# tick-display-mk-3-mini.net
KiCad netlist of a schematic drawn in EAGLE
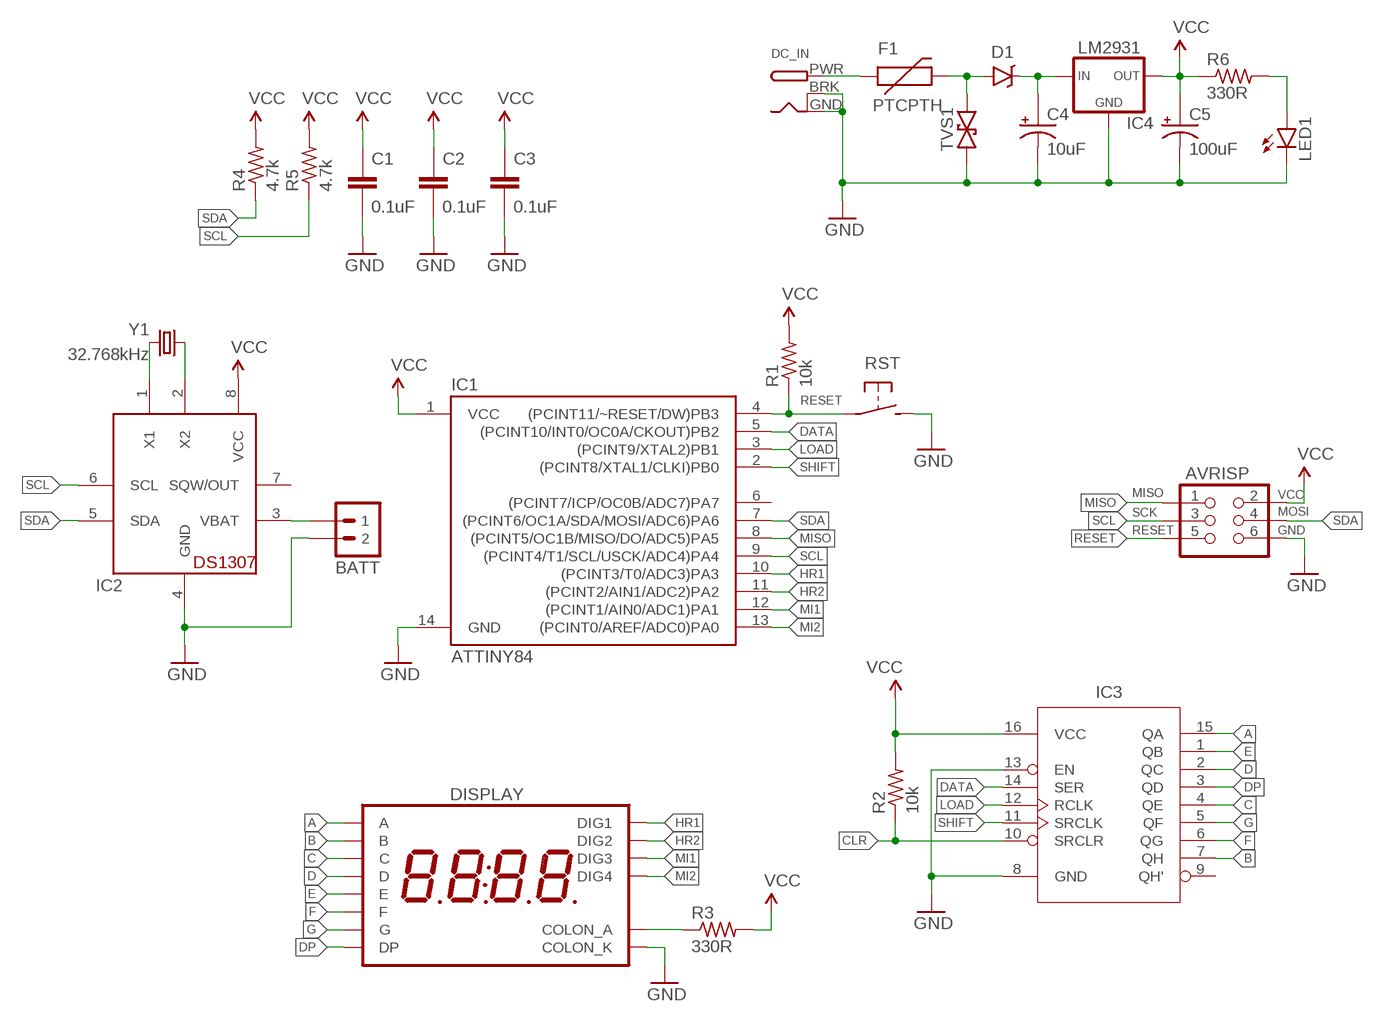
[diagram p0: schematic, sheet 1]

(export (version "E")
  (design (tool "Eeschema 10.0.6"))
  (components
    (comp (ref "AVRISP")
      (value "AVR_SPI_PRG_6PTH")
      (footprint "eagle-import:2X3")
      (libsource (lib "eagle-import") (part "AVR_SPI_PRG_6PTH"))
    )
    (comp (ref "BATT")
      (value "M02JST-PTH-VERT")
      (footprint "eagle-import:JST-2-PH-VERT-PTH")
      (libsource (lib "eagle-import") (part "M02JST-PTH-VERT"))
    )
    (comp (ref "C1")
      (value "0.1uF")
      (footprint "eagle-import:C025-024X044")
      (libsource (lib "eagle-import") (part "CAPACITOR-CERAMIC025-024X044"))
    )
    (comp (ref "C2")
      (value "0.1uF")
      (footprint "eagle-import:C025-024X044")
      (libsource (lib "eagle-import") (part "CAPACITOR-CERAMIC025-024X044"))
    )
    (comp (ref "C3")
      (value "0.1uF")
      (footprint "eagle-import:C025-024X044")
      (libsource (lib "eagle-import") (part "CAPACITOR-CERAMIC025-024X044"))
    )
    (comp (ref "C4")
      (value "10uF")
      (footprint "eagle-import:E2,5-6")
      (libsource (lib "eagle-import") (part "CAPACITOR-POLARIZEDE2.5-6"))
    )
    (comp (ref "C5")
      (value "100uF")
      (footprint "eagle-import:E2,5-6")
      (libsource (lib "eagle-import") (part "CAPACITOR-POLARIZEDE2.5-6"))
    )
    (comp (ref "D1")
      (value "1N5819")
      (footprint "eagle-import:DIODE-7.68MM")
      (libsource (lib "eagle-import") (part "DIODE-SCHOTTKYPTH-7.68MM"))
    )
    (comp (ref "DC_IN")
      (value "DCBARRELPTH")
      (footprint "eagle-import:DCJACK_2MM_PTH")
      (libsource (lib "eagle-import") (part "DCBARRELPTH"))
    )
    (comp (ref "DISPLAY")
      (value "7SED_4DIGIT_14MM14.2MM-CC-NS")
      (footprint "eagle-import:7SEG_4DIG_NS")
      (libsource (lib "eagle-import") (part "7SED_4DIGIT_14MM14.2MM-CC-NS"))
    )
    (comp (ref "F1")
      (value "PTCPTH")
      (footprint "eagle-import:PTC")
      (libsource (lib "eagle-import") (part "PTCPTH"))
    )
    (comp (ref "IC1")
      (value "ATTINY84")
      (footprint "eagle-import:DIL14")
      (libsource (lib "eagle-import") (part "ATTINY84ATTINY84-20PU"))
    )
    (comp (ref "IC2")
      (value "DS1307")
      (footprint "eagle-import:DIL08")
      (libsource (lib "eagle-import") (part "DS1307"))
    )
    (comp (ref "IC3")
      (value "74HCT595")
      (footprint "eagle-import:DIL16")
      (libsource (lib "eagle-import") (part "74595DIP"))
    )
    (comp (ref "IC4")
      (value "LM2931")
      (footprint "eagle-import:TO-92-AMMO")
      (libsource (lib "eagle-import") (part "V_REG_78XXTO-92-INLINE"))
    )
    (comp (ref "LED1")
      (value "LED3MM")
      (footprint "eagle-import:LED3MM")
      (libsource (lib "eagle-import") (part "LED3MM"))
    )
    (comp (ref "R1")
      (value "10k")
      (footprint "eagle-import:RESISTOR-AXIAL-PTH-5.08MM")
      (libsource (lib "eagle-import") (part "RESISTORPTH-AXIAL-5.08MM"))
    )
    (comp (ref "R2")
      (value "10k")
      (footprint "eagle-import:RESISTOR-AXIAL-PTH-5.08MM")
      (libsource (lib "eagle-import") (part "RESISTORPTH-AXIAL-5.08MM"))
    )
    (comp (ref "R3")
      (value "330R")
      (footprint "eagle-import:RESISTOR-AXIAL-PTH-5.08MM")
      (libsource (lib "eagle-import") (part "RESISTORPTH-AXIAL-5.08MM"))
    )
    (comp (ref "R4")
      (value "4.7k")
      (footprint "eagle-import:RESISTOR-AXIAL-PTH-5.08MM")
      (libsource (lib "eagle-import") (part "RESISTORPTH-AXIAL-5.08MM"))
    )
    (comp (ref "R5")
      (value "4.7k")
      (footprint "eagle-import:RESISTOR-AXIAL-PTH-5.08MM")
      (libsource (lib "eagle-import") (part "RESISTORPTH-AXIAL-5.08MM"))
    )
    (comp (ref "R6")
      (value "330R")
      (footprint "eagle-import:RESISTOR-AXIAL-PTH-5.08MM")
      (libsource (lib "eagle-import") (part "RESISTORPTH-AXIAL-5.08MM"))
    )
    (comp (ref "RST")
      (value "SPST-NO-TACT3MM-RA")
      (footprint "eagle-import:TACTILE-PTH-SIDE")
      (libsource (lib "eagle-import") (part "SPST-NO-TACT3MM-RA"))
    )
    (comp (ref "TVS1")
      (value "TVSDO-41-TVS-BIDIRECTIONAL")
      (footprint "eagle-import:DO-41-TVS")
      (libsource (lib "eagle-import") (part "TVSDO-41-TVS-BIDIRECTIONAL"))
    )
    (comp (ref "Y1")
      (value "32.768kHz")
      (footprint "eagle-import:TC26H")
      (libsource (lib "eagle-import") (part "CRYSTALTC26H"))
    )
  )
  (nets
    (net (code "1") (name "A") (class "Default")
      (node (ref "DISPLAY") (pin "P$13") (pinfunction "A_P$13") (pintype "passive"))
      (node (ref "IC3") (pin "15") (pinfunction "QA_15") (pintype "bidirectional"))
    )
    (net (code "2") (name "B") (class "Default")
      (node (ref "DISPLAY") (pin "P$9") (pinfunction "B_P$9") (pintype "passive"))
      (node (ref "IC3") (pin "7") (pinfunction "QH_7") (pintype "bidirectional"))
    )
    (net (code "3") (name "C") (class "Default")
      (node (ref "DISPLAY") (pin "P$4") (pinfunction "C_P$4") (pintype "passive"))
      (node (ref "IC3") (pin "4") (pinfunction "QE_4") (pintype "bidirectional"))
    )
    (net (code "4") (name "CLR") (class "Default")
      (node (ref "IC3") (pin "10") (pinfunction "SRCLR_10") (pintype "bidirectional"))
      (node (ref "R2") (pin "P$1") (pinfunction "1_P$1") (pintype "passive"))
    )
    (net (code "5") (name "D") (class "Default")
      (node (ref "DISPLAY") (pin "P$2") (pinfunction "D_P$2") (pintype "passive"))
      (node (ref "IC3") (pin "2") (pinfunction "QC_2") (pintype "bidirectional"))
    )
    (net (code "6") (name "DATA") (class "Default")
      (node (ref "IC1") (pin "5") (pinfunction "(PCINT10/INT0/OC0A/CKOUT)PB2_5") (pintype "bidirectional"))
      (node (ref "IC3") (pin "14") (pinfunction "SER_14") (pintype "bidirectional"))
    )
    (net (code "7") (name "DP") (class "Default")
      (node (ref "DISPLAY") (pin "P$3") (pinfunction "DP_P$3") (pintype "passive"))
      (node (ref "IC3") (pin "3") (pinfunction "QD_3") (pintype "bidirectional"))
    )
    (net (code "8") (name "E") (class "Default")
      (node (ref "DISPLAY") (pin "P$1") (pinfunction "E_P$1") (pintype "passive"))
      (node (ref "IC3") (pin "1") (pinfunction "QB_1") (pintype "bidirectional"))
    )
    (net (code "9") (name "F") (class "Default")
      (node (ref "DISPLAY") (pin "P$12") (pinfunction "F_P$12") (pintype "passive"))
      (node (ref "IC3") (pin "6") (pinfunction "QG_6") (pintype "bidirectional"))
    )
    (net (code "10") (name "G") (class "Default")
      (node (ref "DISPLAY") (pin "P$5") (pinfunction "G_P$5") (pintype "passive"))
      (node (ref "IC3") (pin "5") (pinfunction "QF_5") (pintype "bidirectional"))
    )
    (net (code "11") (name "GND") (class "Default")
      (node (ref "AVRISP") (pin "6") (pinfunction "GND_6") (pintype "passive"))
      (node (ref "BATT") (pin "2") (pinfunction "2_2") (pintype "passive"))
      (node (ref "C1") (pin "2") (pinfunction "2_2") (pintype "passive"))
      (node (ref "C2") (pin "2") (pinfunction "2_2") (pintype "passive"))
      (node (ref "C3") (pin "2") (pinfunction "2_2") (pintype "passive"))
      (node (ref "C4") (pin "-") (pinfunction "-_-") (pintype "passive"))
      (node (ref "C5") (pin "-") (pinfunction "-_-") (pintype "passive"))
      (node (ref "DC_IN") (pin "BRK") (pinfunction "BRK_BRK") (pintype "power_in"))
      (node (ref "DC_IN") (pin "GND") (pinfunction "GND_GND") (pintype "power_in"))
      (node (ref "DISPLAY") (pin "P$7") (pinfunction "COLON_K_P$7") (pintype "passive"))
      (node (ref "IC1") (pin "14") (pinfunction "GND_14") (pintype "bidirectional"))
      (node (ref "IC2") (pin "4") (pinfunction "GND_4") (pintype "power_in"))
      (node (ref "IC3") (pin "13") (pinfunction "EN_13") (pintype "bidirectional"))
      (node (ref "IC3") (pin "8") (pinfunction "GND_8") (pintype "bidirectional"))
      (node (ref "IC4") (pin "2") (pinfunction "GND_2") (pintype "input"))
      (node (ref "LED1") (pin "K") (pinfunction "C_K") (pintype "passive"))
      (node (ref "RST") (pin "2") (pinfunction "2_2") (pintype "passive"))
      (node (ref "TVS1") (pin "P$1") (pinfunction "1_P$1") (pintype "passive"))
    )
    (net (code "12") (name "HR1") (class "Default")
      (node (ref "DISPLAY") (pin "P$14") (pinfunction "DIG1_P$14") (pintype "passive"))
      (node (ref "IC1") (pin "10") (pinfunction "(PCINT3/T0/ADC3)PA3_10") (pintype "bidirectional"))
    )
    (net (code "13") (name "HR2") (class "Default")
      (node (ref "DISPLAY") (pin "P$11") (pinfunction "DIG2_P$11") (pintype "passive"))
      (node (ref "IC1") (pin "11") (pinfunction "(PCINT2/AIN1/ADC2)PA2_11") (pintype "bidirectional"))
    )
    (net (code "14") (name "LOAD") (class "Default")
      (node (ref "IC1") (pin "3") (pinfunction "(PCINT9/XTAL2)PB1_3") (pintype "bidirectional"))
      (node (ref "IC3") (pin "12") (pinfunction "RCLK_12") (pintype "bidirectional"))
    )
    (net (code "15") (name "MI1") (class "Default")
      (node (ref "DISPLAY") (pin "P$10") (pinfunction "DIG3_P$10") (pintype "passive"))
      (node (ref "IC1") (pin "12") (pinfunction "(PCINT1/AIN0/ADC1)PA1_12") (pintype "bidirectional"))
    )
    (net (code "16") (name "MI2") (class "Default")
      (node (ref "DISPLAY") (pin "P$6") (pinfunction "DIG4_P$6") (pintype "passive"))
      (node (ref "IC1") (pin "13") (pinfunction "(PCINT0/AREF/ADC0)PA0_13") (pintype "bidirectional"))
    )
    (net (code "17") (name "MISO") (class "Default")
      (node (ref "AVRISP") (pin "1") (pinfunction "MISO_1") (pintype "passive"))
      (node (ref "IC1") (pin "8") (pinfunction "(PCINT5/OC1B/MISO/DO/ADC5)PA5_8") (pintype "bidirectional"))
    )
    (net (code "18") (name "Net-(D1-C)") (class "Default")
      (node (ref "C4") (pin "+") (pinfunction "+_+") (pintype "passive"))
      (node (ref "D1") (pin "K") (pinfunction "C_K") (pintype "passive"))
      (node (ref "IC4") (pin "1") (pinfunction "IN_1") (pintype "input"))
    )
    (net (code "19") (name "Net-(DISPLAY-COLON_A)") (class "Default")
      (node (ref "DISPLAY") (pin "P$8") (pinfunction "COLON_A_P$8") (pintype "passive"))
      (node (ref "R3") (pin "P$1") (pinfunction "1_P$1") (pintype "passive"))
    )
    (net (code "20") (name "Net-(F1-1)") (class "Default")
      (node (ref "DC_IN") (pin "PWR") (pinfunction "PWR_PWR") (pintype "power_in"))
      (node (ref "F1") (pin "P$1") (pinfunction "1_P$1") (pintype "bidirectional"))
    )
    (net (code "21") (name "Net-(F1-2)") (class "Default")
      (node (ref "D1") (pin "A") (pinfunction "A_A") (pintype "passive"))
      (node (ref "F1") (pin "P$2") (pinfunction "2_P$2") (pintype "bidirectional"))
      (node (ref "TVS1") (pin "P$2") (pinfunction "2_P$2") (pintype "passive"))
    )
    (net (code "22") (name "Net-(IC2-VBAT)") (class "Default")
      (node (ref "BATT") (pin "1") (pinfunction "1_1") (pintype "passive"))
      (node (ref "IC2") (pin "3") (pinfunction "VBAT_3") (pintype "power_in"))
    )
    (net (code "23") (name "Net-(IC2-X1)") (class "Default")
      (node (ref "IC2") (pin "1") (pinfunction "X1_1") (pintype "passive"))
      (node (ref "Y1") (pin "2") (pinfunction "2_2") (pintype "passive"))
    )
    (net (code "24") (name "Net-(IC2-X2)") (class "Default")
      (node (ref "IC2") (pin "2") (pinfunction "X2_2") (pintype "passive"))
      (node (ref "Y1") (pin "1") (pinfunction "1_1") (pintype "passive"))
    )
    (net (code "25") (name "Net-(R6-2)") (class "Default")
      (node (ref "LED1") (pin "A") (pinfunction "A_A") (pintype "passive"))
      (node (ref "R6") (pin "P$2") (pinfunction "2_P$2") (pintype "passive"))
    )
    (net (code "26") (name "RESET") (class "Default")
      (node (ref "AVRISP") (pin "5") (pinfunction "RESET_5") (pintype "passive"))
      (node (ref "IC1") (pin "4") (pinfunction "(PCINT11/~{RESET/DW})PB3_4") (pintype "bidirectional"))
      (node (ref "R1") (pin "P$1") (pinfunction "1_P$1") (pintype "passive"))
      (node (ref "RST") (pin "1") (pinfunction "1_1") (pintype "passive"))
    )
    (net (code "27") (name "SCL") (class "Default")
      (node (ref "AVRISP") (pin "3") (pinfunction "SCK_3") (pintype "passive"))
      (node (ref "IC1") (pin "9") (pinfunction "(PCINT4/T1/SCL/USCK/ADC4)PA4_9") (pintype "bidirectional"))
      (node (ref "IC2") (pin "6") (pinfunction "SCL_6") (pintype "bidirectional"))
      (node (ref "R5") (pin "P$1") (pinfunction "1_P$1") (pintype "passive"))
    )
    (net (code "28") (name "SDA") (class "Default")
      (node (ref "AVRISP") (pin "4") (pinfunction "MOSI_4") (pintype "passive"))
      (node (ref "IC1") (pin "7") (pinfunction "(PCINT6/OC1A/SDA/MOSI/ADC6)PA6_7") (pintype "bidirectional"))
      (node (ref "IC2") (pin "5") (pinfunction "SDA_5") (pintype "bidirectional"))
      (node (ref "R4") (pin "P$1") (pinfunction "1_P$1") (pintype "passive"))
    )
    (net (code "29") (name "SHIFT") (class "Default")
      (node (ref "IC1") (pin "2") (pinfunction "(PCINT8/XTAL1/CLKI)PB0_2") (pintype "bidirectional"))
      (node (ref "IC3") (pin "11") (pinfunction "SRCLK_11") (pintype "bidirectional"))
    )
    (net (code "30") (name "VCC") (class "Default")
      (node (ref "AVRISP") (pin "2") (pinfunction "VCC_2") (pintype "passive"))
      (node (ref "C1") (pin "1") (pinfunction "1_1") (pintype "passive"))
      (node (ref "C2") (pin "1") (pinfunction "1_1") (pintype "passive"))
      (node (ref "C3") (pin "1") (pinfunction "1_1") (pintype "passive"))
      (node (ref "C5") (pin "+") (pinfunction "+_+") (pintype "passive"))
      (node (ref "IC1") (pin "1") (pinfunction "VCC_1") (pintype "bidirectional"))
      (node (ref "IC2") (pin "8") (pinfunction "VCC_8") (pintype "power_in"))
      (node (ref "IC3") (pin "16") (pinfunction "VCC_16") (pintype "bidirectional"))
      (node (ref "IC4") (pin "3") (pinfunction "OUT_3") (pintype "output"))
      (node (ref "R1") (pin "P$2") (pinfunction "2_P$2") (pintype "passive"))
      (node (ref "R2") (pin "P$2") (pinfunction "2_P$2") (pintype "passive"))
      (node (ref "R3") (pin "P$2") (pinfunction "2_P$2") (pintype "passive"))
      (node (ref "R4") (pin "P$2") (pinfunction "2_P$2") (pintype "passive"))
      (node (ref "R5") (pin "P$2") (pinfunction "2_P$2") (pintype "passive"))
      (node (ref "R6") (pin "P$1") (pinfunction "1_P$1") (pintype "passive"))
    )
    (net (code "31") (name "unconnected-(IC1-(PCINT7{slash}ICP{slash}OC0B{slash}ADC7)PA7-Pad6)") (class "Default")
      (node (ref "IC1") (pin "6") (pinfunction "(PCINT7/ICP/OC0B/ADC7)PA7_6") (pintype "bidirectional"))
    )
    (net (code "32") (name "unconnected-(IC2-SQW{slash}OUT-Pad7)") (class "Default")
      (node (ref "IC2") (pin "7") (pinfunction "SQW/OUT_7") (pintype "bidirectional"))
    )
    (net (code "33") (name "unconnected-(IC3-QH'-Pad9)") (class "Default")
      (node (ref "IC3") (pin "9") (pinfunction "QH'_9") (pintype "bidirectional"))
    )
  )
)
